# Pi3B__Adapter.net
KiCad netlist of a schematic drawn in EAGLE
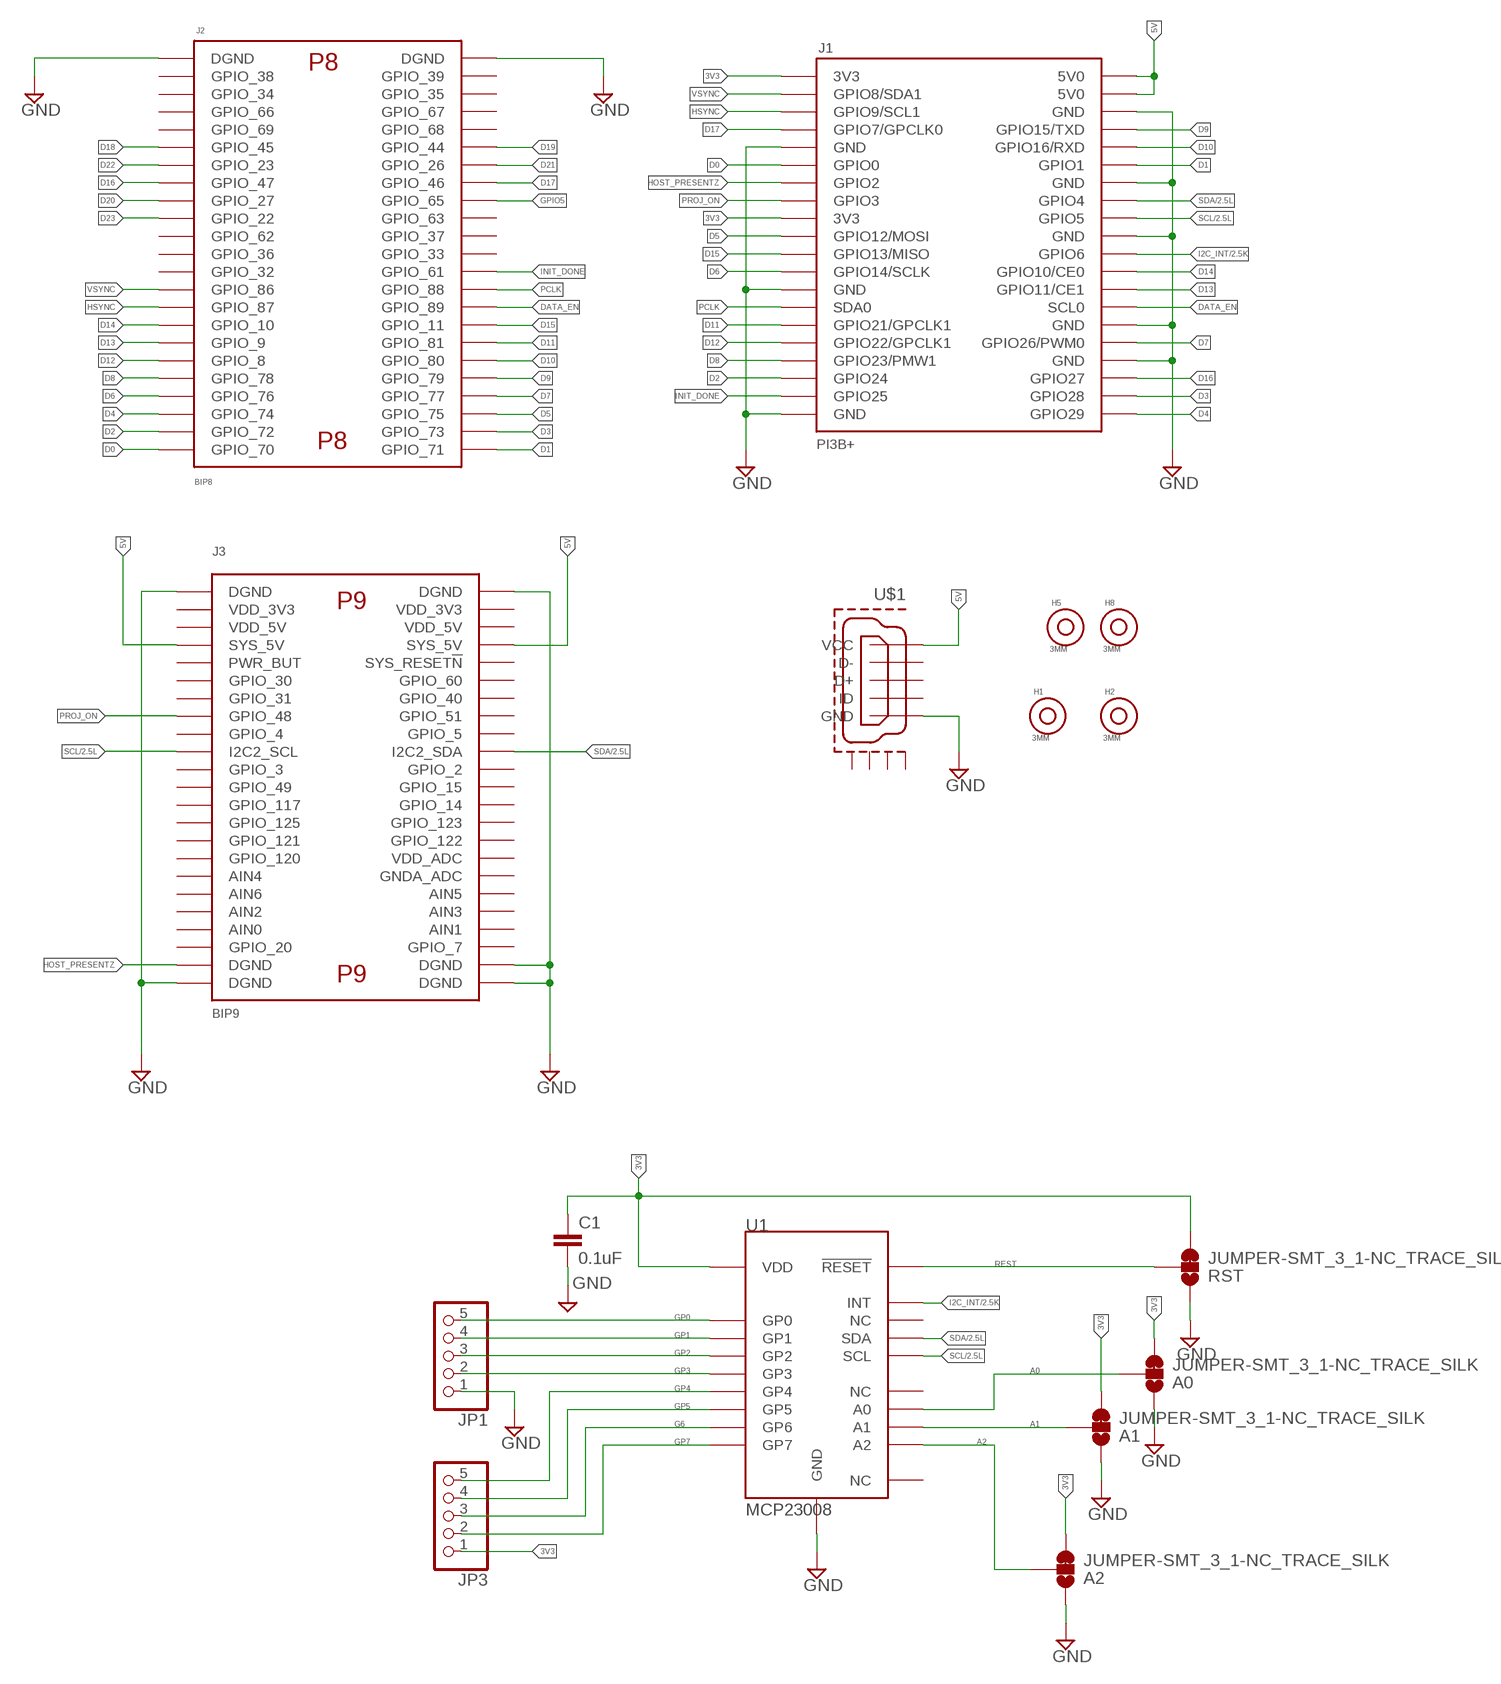
[diagram p0: schematic, sheet 1]

(export (version "E")
  (design (tool "Eeschema 10.0.6"))
  (components
    (comp (ref "A0")
      (value "JUMPER-SMT_3_1-NC_TRACE_SILK")
      (footprint "eagle-import:SMT-JUMPER_3_1-NC_TRACE_SILK")
      (libsource (lib "eagle-import") (part "JUMPER-SMT_3_1-NC_TRACE_SILK"))
    )
    (comp (ref "A1")
      (value "JUMPER-SMT_3_1-NC_TRACE_SILK")
      (footprint "eagle-import:SMT-JUMPER_3_1-NC_TRACE_SILK")
      (libsource (lib "eagle-import") (part "JUMPER-SMT_3_1-NC_TRACE_SILK"))
    )
    (comp (ref "A2")
      (value "JUMPER-SMT_3_1-NC_TRACE_SILK")
      (footprint "eagle-import:SMT-JUMPER_3_1-NC_TRACE_SILK")
      (libsource (lib "eagle-import") (part "JUMPER-SMT_3_1-NC_TRACE_SILK"))
    )
    (comp (ref "C1")
      (value "0.1uF")
      (footprint "eagle-import:0402")
      (libsource (lib "eagle-import") (part "0.1UF-0402-16V-10%"))
    )
    (comp (ref "H1")
      (value "3MM")
      (footprint "eagle-import:3MM")
      (libsource (lib "eagle-import") (part "3MM"))
    )
    (comp (ref "H2")
      (value "3MM")
      (footprint "eagle-import:3MM")
      (libsource (lib "eagle-import") (part "3MM"))
    )
    (comp (ref "H5")
      (value "3MM")
      (footprint "eagle-import:3MM")
      (libsource (lib "eagle-import") (part "3MM"))
    )
    (comp (ref "H8")
      (value "3MM")
      (footprint "eagle-import:3MM")
      (libsource (lib "eagle-import") (part "3MM"))
    )
    (comp (ref "J1")
      (value "PI3B+")
      (footprint "eagle-import:PI3B+")
      (libsource (lib "eagle-import") (part "PI3B+"))
    )
    (comp (ref "J2")
      (value "BIP8")
      (footprint "eagle-import:BIP8")
      (libsource (lib "eagle-import") (part "BIP8"))
    )
    (comp (ref "J3")
      (value "BIP9")
      (footprint "eagle-import:BIP9")
      (libsource (lib "eagle-import") (part "BIP9"))
    )
    (comp (ref "JP1")
      (value "PINHD-1X55X2MM")
      (footprint "eagle-import:1_05X2MM")
      (libsource (lib "eagle-import") (part "PINHD-1X55X2MM"))
    )
    (comp (ref "JP3")
      (value "PINHD-1X55X2MM")
      (footprint "eagle-import:1_05X2MM")
      (libsource (lib "eagle-import") (part "PINHD-1X55X2MM"))
    )
    (comp (ref "RST")
      (value "JUMPER-SMT_3_1-NC_TRACE_SILK")
      (footprint "eagle-import:SMT-JUMPER_3_1-NC_TRACE_SILK")
      (libsource (lib "eagle-import") (part "JUMPER-SMT_3_1-NC_TRACE_SILK"))
    )
    (comp (ref "U$1")
      (value "MICRO-USB-RECEPTACLE47589-0001")
      (footprint "eagle-import:47589-0001")
      (libsource (lib "eagle-import") (part "MICRO-USB-RECEPTACLE47589-0001"))
    )
    (comp (ref "U1")
      (value "MCP23008")
      (footprint "eagle-import:MCP23008SS")
      (libsource (lib "eagle-import") (part "MCP23008"))
    )
  )
  (nets
    (net (code "1") (name "/A0") (class "Default")
      (node (ref "A0") (pin "2") (pinfunction "2_2") (pintype "passive"))
      (node (ref "U1") (pin "A0") (pinfunction "A0_A0") (pintype "bidirectional"))
    )
    (net (code "2") (name "/A1") (class "Default")
      (node (ref "A1") (pin "2") (pinfunction "2_2") (pintype "passive"))
      (node (ref "U1") (pin "A1") (pinfunction "A1_A1") (pintype "bidirectional"))
    )
    (net (code "3") (name "/A2") (class "Default")
      (node (ref "A2") (pin "2") (pinfunction "2_2") (pintype "passive"))
      (node (ref "U1") (pin "A2") (pinfunction "A2_A2") (pintype "bidirectional"))
    )
    (net (code "4") (name "/G6") (class "Default")
      (node (ref "JP3") (pin "3") (pinfunction "3_3") (pintype "passive"))
      (node (ref "U1") (pin "GP6") (pinfunction "GP6_GP6") (pintype "bidirectional"))
    )
    (net (code "5") (name "/GP0") (class "Default")
      (node (ref "JP1") (pin "5") (pinfunction "5_5") (pintype "passive"))
      (node (ref "U1") (pin "GP0") (pinfunction "GP0_GP0") (pintype "bidirectional"))
    )
    (net (code "6") (name "/GP1") (class "Default")
      (node (ref "JP1") (pin "4") (pinfunction "4_4") (pintype "passive"))
      (node (ref "U1") (pin "GP1") (pinfunction "GP1_GP1") (pintype "bidirectional"))
    )
    (net (code "7") (name "/GP2") (class "Default")
      (node (ref "JP1") (pin "3") (pinfunction "3_3") (pintype "passive"))
      (node (ref "U1") (pin "GP2") (pinfunction "GP2_GP2") (pintype "bidirectional"))
    )
    (net (code "8") (name "/GP3") (class "Default")
      (node (ref "JP1") (pin "2") (pinfunction "2_2") (pintype "passive"))
      (node (ref "U1") (pin "GP3") (pinfunction "GP3_GP3") (pintype "bidirectional"))
    )
    (net (code "9") (name "/GP4") (class "Default")
      (node (ref "JP3") (pin "5") (pinfunction "5_5") (pintype "passive"))
      (node (ref "U1") (pin "GP4") (pinfunction "GP4_GP4") (pintype "bidirectional"))
    )
    (net (code "10") (name "/GP5") (class "Default")
      (node (ref "JP3") (pin "4") (pinfunction "4_4") (pintype "passive"))
      (node (ref "U1") (pin "GP5") (pinfunction "GP5_GP5") (pintype "bidirectional"))
    )
    (net (code "11") (name "/GP7") (class "Default")
      (node (ref "JP3") (pin "2") (pinfunction "2_2") (pintype "passive"))
      (node (ref "U1") (pin "GP7") (pinfunction "GP7_GP7") (pintype "bidirectional"))
    )
    (net (code "12") (name "/REST") (class "Default")
      (node (ref "RST") (pin "2") (pinfunction "2_2") (pintype "passive"))
      (node (ref "U1") (pin "!RESET") (pinfunction "~{RESET}_!RESET") (pintype "bidirectional"))
    )
    (net (code "13") (name "3V3") (class "Default")
      (node (ref "A0") (pin "3") (pinfunction "3_3") (pintype "passive"))
      (node (ref "A1") (pin "3") (pinfunction "3_3") (pintype "passive"))
      (node (ref "A2") (pin "3") (pinfunction "3_3") (pintype "passive"))
      (node (ref "C1") (pin "1") (pinfunction "1_1") (pintype "passive"))
      (node (ref "J1") (pin "3V3") (pinfunction "3V3_3V3") (pintype "bidirectional"))
      (node (ref "J1") (pin "3V3@1") (pinfunction "3V3_3V3@1") (pintype "bidirectional"))
      (node (ref "JP3") (pin "1") (pinfunction "1_1") (pintype "passive"))
      (node (ref "RST") (pin "3") (pinfunction "3_3") (pintype "passive"))
      (node (ref "U1") (pin "VDD") (pinfunction "VDD_VDD") (pintype "bidirectional"))
    )
    (net (code "14") (name "5V") (class "Default")
      (node (ref "J1") (pin "5V0") (pinfunction "5V0_5V0") (pintype "bidirectional"))
      (node (ref "J1") (pin "5V0@1") (pinfunction "5V0_5V0@1") (pintype "bidirectional"))
      (node (ref "J3") (pin "SYS_5V") (pinfunction "SYS_5V_SYS_5V") (pintype "bidirectional"))
      (node (ref "J3") (pin "SYS_5V@1") (pinfunction "SYS_5V_SYS_5V@1") (pintype "bidirectional"))
      (node (ref "U$1") (pin "V-BUS") (pinfunction "VCC_V-BUS") (pintype "input"))
    )
    (net (code "15") (name "D0") (class "Default")
      (node (ref "J1") (pin "GPIO0") (pinfunction "GPIO0_GPIO0") (pintype "bidirectional"))
      (node (ref "J2") (pin "GPIO_70") (pinfunction "GPIO_70_GPIO_70") (pintype "bidirectional"))
    )
    (net (code "16") (name "D1") (class "Default")
      (node (ref "J1") (pin "GPIO1") (pinfunction "GPIO1_GPIO1") (pintype "bidirectional"))
      (node (ref "J2") (pin "GPIO_71") (pinfunction "GPIO_71_GPIO_71") (pintype "bidirectional"))
    )
    (net (code "17") (name "D2") (class "Default")
      (node (ref "J1") (pin "GPIO24") (pinfunction "GPIO24_GPIO24") (pintype "bidirectional"))
      (node (ref "J2") (pin "GPIO_72") (pinfunction "GPIO_72_GPIO_72") (pintype "bidirectional"))
    )
    (net (code "18") (name "D3") (class "Default")
      (node (ref "J1") (pin "GPIO28") (pinfunction "GPIO28_GPIO28") (pintype "bidirectional"))
      (node (ref "J2") (pin "GPIO_73") (pinfunction "GPIO_73_GPIO_73") (pintype "bidirectional"))
    )
    (net (code "19") (name "D4") (class "Default")
      (node (ref "J1") (pin "GPIO29") (pinfunction "GPIO29_GPIO29") (pintype "bidirectional"))
      (node (ref "J2") (pin "GPIO_74") (pinfunction "GPIO_74_GPIO_74") (pintype "bidirectional"))
    )
    (net (code "20") (name "D5") (class "Default")
      (node (ref "J1") (pin "GPIO12/MOSI") (pinfunction "GPIO12/MOSI_GPIO12/MOSI") (pintype "bidirectional"))
      (node (ref "J2") (pin "GPIO_75") (pinfunction "GPIO_75_GPIO_75") (pintype "bidirectional"))
    )
    (net (code "21") (name "D6") (class "Default")
      (node (ref "J1") (pin "GPIO14/SCLK") (pinfunction "GPIO14/SCLK_GPIO14/SCLK") (pintype "bidirectional"))
      (node (ref "J2") (pin "GPIO_76") (pinfunction "GPIO_76_GPIO_76") (pintype "bidirectional"))
    )
    (net (code "22") (name "D7") (class "Default")
      (node (ref "J1") (pin "GPIO26/PMW0") (pinfunction "GPIO26/PWM0_GPIO26/PMW0") (pintype "bidirectional"))
      (node (ref "J2") (pin "GPIO_77") (pinfunction "GPIO_77_GPIO_77") (pintype "bidirectional"))
    )
    (net (code "23") (name "D8") (class "Default")
      (node (ref "J1") (pin "GPIO23/PWM1") (pinfunction "GPIO23/PMW1_GPIO23/PWM1") (pintype "bidirectional"))
      (node (ref "J2") (pin "GPIO_78") (pinfunction "GPIO_78_GPIO_78") (pintype "bidirectional"))
    )
    (net (code "24") (name "D9") (class "Default")
      (node (ref "J1") (pin "GPIO15/TXD") (pinfunction "GPIO15/TXD_GPIO15/TXD") (pintype "bidirectional"))
      (node (ref "J2") (pin "GPIO_79") (pinfunction "GPIO_79_GPIO_79") (pintype "bidirectional"))
    )
    (net (code "25") (name "D10") (class "Default")
      (node (ref "J1") (pin "GPIO16/RXD") (pinfunction "GPIO16/RXD_GPIO16/RXD") (pintype "bidirectional"))
      (node (ref "J2") (pin "GPIO_80") (pinfunction "GPIO_80_GPIO_80") (pintype "bidirectional"))
    )
    (net (code "26") (name "D11") (class "Default")
      (node (ref "J1") (pin "GPIO21/GPCLK1") (pinfunction "GPIO21/GPCLK1_GPIO21/GPCLK1") (pintype "bidirectional"))
      (node (ref "J2") (pin "GPIO_81") (pinfunction "GPIO_81_GPIO_81") (pintype "bidirectional"))
    )
    (net (code "27") (name "D12") (class "Default")
      (node (ref "J1") (pin "GPIO22/GPCLK2") (pinfunction "GPIO22/GPCLK1_GPIO22/GPCLK2") (pintype "bidirectional"))
      (node (ref "J2") (pin "GPIO_8") (pinfunction "GPIO_8_GPIO_8") (pintype "bidirectional"))
    )
    (net (code "28") (name "D13") (class "Default")
      (node (ref "J1") (pin "GPIO11/CE1") (pinfunction "GPIO11/CE1_GPIO11/CE1") (pintype "bidirectional"))
      (node (ref "J2") (pin "GPIO_9") (pinfunction "GPIO_9_GPIO_9") (pintype "bidirectional"))
    )
    (net (code "29") (name "D14") (class "Default")
      (node (ref "J1") (pin "GPIO10/CE0") (pinfunction "GPIO10/CE0_GPIO10/CE0") (pintype "bidirectional"))
      (node (ref "J2") (pin "GPIO_10") (pinfunction "GPIO_10_GPIO_10") (pintype "bidirectional"))
    )
    (net (code "30") (name "D15") (class "Default")
      (node (ref "J1") (pin "GPIO13/MISO") (pinfunction "GPIO13/MISO_GPIO13/MISO") (pintype "bidirectional"))
      (node (ref "J2") (pin "GPIO_11") (pinfunction "GPIO_11_GPIO_11") (pintype "bidirectional"))
    )
    (net (code "31") (name "D16") (class "Default")
      (node (ref "J1") (pin "GPIO27") (pinfunction "GPIO27_GPIO27") (pintype "bidirectional"))
      (node (ref "J2") (pin "GPIO_47") (pinfunction "GPIO_47_GPIO_47") (pintype "bidirectional"))
    )
    (net (code "32") (name "D17") (class "Default")
      (node (ref "J1") (pin "GPIO7/GPCLK0") (pinfunction "GPIO7/GPCLK0_GPIO7/GPCLK0") (pintype "bidirectional"))
      (node (ref "J2") (pin "GPIO_46") (pinfunction "GPIO_46_GPIO_46") (pintype "bidirectional"))
    )
    (net (code "33") (name "D18") (class "Default")
      (node (ref "J2") (pin "GPIO_45") (pinfunction "GPIO_45_GPIO_45") (pintype "bidirectional"))
    )
    (net (code "34") (name "D19") (class "Default")
      (node (ref "J2") (pin "GPIO_44") (pinfunction "GPIO_44_GPIO_44") (pintype "bidirectional"))
    )
    (net (code "35") (name "D20") (class "Default")
      (node (ref "J2") (pin "GPIO_27") (pinfunction "GPIO_27_GPIO_27") (pintype "bidirectional"))
    )
    (net (code "36") (name "D21") (class "Default")
      (node (ref "J2") (pin "GPIO_26") (pinfunction "GPIO_26_GPIO_26") (pintype "bidirectional"))
    )
    (net (code "37") (name "D22") (class "Default")
      (node (ref "J2") (pin "GPIO_23") (pinfunction "GPIO_23_GPIO_23") (pintype "bidirectional"))
    )
    (net (code "38") (name "D23") (class "Default")
      (node (ref "J2") (pin "GPIO_22") (pinfunction "GPIO_22_GPIO_22") (pintype "bidirectional"))
    )
    (net (code "39") (name "DATA_EN") (class "Default")
      (node (ref "J1") (pin "SCL0") (pinfunction "SCL0_SCL0") (pintype "bidirectional"))
      (node (ref "J2") (pin "GPIO_89") (pinfunction "GPIO_89_GPIO_89") (pintype "bidirectional"))
    )
    (net (code "40") (name "GND") (class "Default")
      (node (ref "A0") (pin "1") (pinfunction "1_1") (pintype "passive"))
      (node (ref "A1") (pin "1") (pinfunction "1_1") (pintype "passive"))
      (node (ref "A2") (pin "1") (pinfunction "1_1") (pintype "passive"))
      (node (ref "C1") (pin "2") (pinfunction "2_2") (pintype "passive"))
      (node (ref "J1") (pin "GND") (pinfunction "GND_GND") (pintype "bidirectional"))
      (node (ref "J1") (pin "GND@1") (pinfunction "GND_GND@1") (pintype "bidirectional"))
      (node (ref "J1") (pin "GND@2") (pinfunction "GND_GND@2") (pintype "bidirectional"))
      (node (ref "J1") (pin "GND@3") (pinfunction "GND_GND@3") (pintype "bidirectional"))
      (node (ref "J1") (pin "GND@4") (pinfunction "GND_GND@4") (pintype "bidirectional"))
      (node (ref "J1") (pin "GND@5") (pinfunction "GND_GND@5") (pintype "bidirectional"))
      (node (ref "J1") (pin "GND@6") (pinfunction "GND_GND@6") (pintype "bidirectional"))
      (node (ref "J1") (pin "GND@7") (pinfunction "GND_GND@7") (pintype "bidirectional"))
      (node (ref "J2") (pin "DGND") (pinfunction "DGND_DGND") (pintype "bidirectional"))
      (node (ref "J2") (pin "DGND@1") (pinfunction "DGND_DGND@1") (pintype "bidirectional"))
      (node (ref "J3") (pin "DGND") (pinfunction "DGND_DGND") (pintype "bidirectional"))
      (node (ref "J3") (pin "DGND@1") (pinfunction "DGND_DGND@1") (pintype "bidirectional"))
      (node (ref "J3") (pin "DGND@4") (pinfunction "DGND_DGND@4") (pintype "bidirectional"))
      (node (ref "J3") (pin "DGND@5") (pinfunction "DGND_DGND@5") (pintype "bidirectional"))
      (node (ref "J3") (pin "DGND@6") (pinfunction "DGND_DGND@6") (pintype "bidirectional"))
      (node (ref "JP1") (pin "1") (pinfunction "1_1") (pintype "passive"))
      (node (ref "RST") (pin "1") (pinfunction "1_1") (pintype "passive"))
      (node (ref "U$1") (pin "GND") (pinfunction "GND_GND") (pintype "input"))
      (node (ref "U1") (pin "GND") (pinfunction "GND_GND") (pintype "bidirectional"))
    )
    (net (code "41") (name "GPIO5") (class "Default")
      (node (ref "J2") (pin "GPIO_65") (pinfunction "GPIO_65_GPIO_65") (pintype "bidirectional"))
    )
    (net (code "42") (name "HOST_PRESENTZ") (class "Default")
      (node (ref "J1") (pin "GPIO2") (pinfunction "GPIO2_GPIO2") (pintype "bidirectional"))
      (node (ref "J3") (pin "DGND@3") (pinfunction "DGND_DGND@3") (pintype "bidirectional"))
    )
    (net (code "43") (name "HSYNC") (class "Default")
      (node (ref "J1") (pin "GPIO9/SCL1") (pinfunction "GPIO9/SCL1_GPIO9/SCL1") (pintype "bidirectional"))
      (node (ref "J2") (pin "GPIO_87") (pinfunction "GPIO_87_GPIO_87") (pintype "bidirectional"))
    )
    (net (code "44") (name "I2C_INT{slash}2.5K") (class "Default")
      (node (ref "J1") (pin "GPIO6") (pinfunction "GPIO6_GPIO6") (pintype "bidirectional"))
      (node (ref "U1") (pin "INT") (pinfunction "INT_INT") (pintype "bidirectional"))
    )
    (net (code "45") (name "INIT_DONE") (class "Default")
      (node (ref "J1") (pin "GPIO25") (pinfunction "GPIO25_GPIO25") (pintype "bidirectional"))
      (node (ref "J2") (pin "GPIO_61") (pinfunction "GPIO_61_GPIO_61") (pintype "bidirectional"))
    )
    (net (code "46") (name "PCLK") (class "Default")
      (node (ref "J1") (pin "SDA0") (pinfunction "SDA0_SDA0") (pintype "bidirectional"))
      (node (ref "J2") (pin "GPIO_88") (pinfunction "GPIO_88_GPIO_88") (pintype "bidirectional"))
    )
    (net (code "47") (name "PROJ_ON") (class "Default")
      (node (ref "J1") (pin "GPIO3") (pinfunction "GPIO3_GPIO3") (pintype "bidirectional"))
      (node (ref "J3") (pin "GPIO_48") (pinfunction "GPIO_48_GPIO_48") (pintype "bidirectional"))
    )
    (net (code "48") (name "SCL{slash}2.5L") (class "Default")
      (node (ref "J1") (pin "GPIO5") (pinfunction "GPIO5_GPIO5") (pintype "bidirectional"))
      (node (ref "J3") (pin "I2C2_SCL") (pinfunction "I2C2_SCL_I2C2_SCL") (pintype "bidirectional"))
      (node (ref "U1") (pin "SCL") (pinfunction "SCL_SCL") (pintype "bidirectional"))
    )
    (net (code "49") (name "SDA{slash}2.5L") (class "Default")
      (node (ref "J1") (pin "GPIO4") (pinfunction "GPIO4_GPIO4") (pintype "bidirectional"))
      (node (ref "J3") (pin "I2C2_SDA") (pinfunction "I2C2_SDA_I2C2_SDA") (pintype "bidirectional"))
      (node (ref "U1") (pin "SDA") (pinfunction "SDA_SDA") (pintype "bidirectional"))
    )
    (net (code "50") (name "VSYNC") (class "Default")
      (node (ref "J1") (pin "GPIO8/SDA1") (pinfunction "GPIO8/SDA1_GPIO8/SDA1") (pintype "bidirectional"))
      (node (ref "J2") (pin "GPIO_86") (pinfunction "GPIO_86_GPIO_86") (pintype "bidirectional"))
    )
    (net (code "51") (name "unconnected-(J2-PadGPIO_32)") (class "Default")
      (node (ref "J2") (pin "GPIO_32") (pinfunction "GPIO_32_GPIO_32") (pintype "bidirectional"))
    )
    (net (code "52") (name "unconnected-(J2-PadGPIO_33)") (class "Default")
      (node (ref "J2") (pin "GPIO_33") (pinfunction "GPIO_33_GPIO_33") (pintype "bidirectional"))
    )
    (net (code "53") (name "unconnected-(J2-PadGPIO_34)") (class "Default")
      (node (ref "J2") (pin "GPIO_34") (pinfunction "GPIO_34_GPIO_34") (pintype "bidirectional"))
    )
    (net (code "54") (name "unconnected-(J2-PadGPIO_35)") (class "Default")
      (node (ref "J2") (pin "GPIO_35") (pinfunction "GPIO_35_GPIO_35") (pintype "bidirectional"))
    )
    (net (code "55") (name "unconnected-(J2-PadGPIO_36)") (class "Default")
      (node (ref "J2") (pin "GPIO_36") (pinfunction "GPIO_36_GPIO_36") (pintype "bidirectional"))
    )
    (net (code "56") (name "unconnected-(J2-PadGPIO_37)") (class "Default")
      (node (ref "J2") (pin "GPIO_37") (pinfunction "GPIO_37_GPIO_37") (pintype "bidirectional"))
    )
    (net (code "57") (name "unconnected-(J2-PadGPIO_38)") (class "Default")
      (node (ref "J2") (pin "GPIO_38") (pinfunction "GPIO_38_GPIO_38") (pintype "bidirectional"))
    )
    (net (code "58") (name "unconnected-(J2-PadGPIO_39)") (class "Default")
      (node (ref "J2") (pin "GPIO_39") (pinfunction "GPIO_39_GPIO_39") (pintype "bidirectional"))
    )
    (net (code "59") (name "unconnected-(J2-PadGPIO_62)") (class "Default")
      (node (ref "J2") (pin "GPIO_62") (pinfunction "GPIO_62_GPIO_62") (pintype "bidirectional"))
    )
    (net (code "60") (name "unconnected-(J2-PadGPIO_63)") (class "Default")
      (node (ref "J2") (pin "GPIO_63") (pinfunction "GPIO_63_GPIO_63") (pintype "bidirectional"))
    )
    (net (code "61") (name "unconnected-(J2-PadGPIO_66)") (class "Default")
      (node (ref "J2") (pin "GPIO_66") (pinfunction "GPIO_66_GPIO_66") (pintype "bidirectional"))
    )
    (net (code "62") (name "unconnected-(J2-PadGPIO_67)") (class "Default")
      (node (ref "J2") (pin "GPIO_67") (pinfunction "GPIO_67_GPIO_67") (pintype "bidirectional"))
    )
    (net (code "63") (name "unconnected-(J2-PadGPIO_68)") (class "Default")
      (node (ref "J2") (pin "GPIO_68") (pinfunction "GPIO_68_GPIO_68") (pintype "bidirectional"))
    )
    (net (code "64") (name "unconnected-(J2-PadGPIO_69)") (class "Default")
      (node (ref "J2") (pin "GPIO_69") (pinfunction "GPIO_69_GPIO_69") (pintype "bidirectional"))
    )
    (net (code "65") (name "unconnected-(J3-PadAIN0)") (class "Default")
      (node (ref "J3") (pin "AIN0") (pinfunction "AIN0_AIN0") (pintype "bidirectional"))
    )
    (net (code "66") (name "unconnected-(J3-PadAIN1)") (class "Default")
      (node (ref "J3") (pin "AIN1") (pinfunction "AIN1_AIN1") (pintype "bidirectional"))
    )
    (net (code "67") (name "unconnected-(J3-PadAIN2)") (class "Default")
      (node (ref "J3") (pin "AIN2") (pinfunction "AIN2_AIN2") (pintype "bidirectional"))
    )
    (net (code "68") (name "unconnected-(J3-PadAIN3)") (class "Default")
      (node (ref "J3") (pin "AIN3") (pinfunction "AIN3_AIN3") (pintype "bidirectional"))
    )
    (net (code "69") (name "unconnected-(J3-PadAIN4)") (class "Default")
      (node (ref "J3") (pin "AIN4") (pinfunction "AIN4_AIN4") (pintype "bidirectional"))
    )
    (net (code "70") (name "unconnected-(J3-PadAIN5)") (class "Default")
      (node (ref "J3") (pin "AIN5") (pinfunction "AIN5_AIN5") (pintype "bidirectional"))
    )
    (net (code "71") (name "unconnected-(J3-PadAIN6)") (class "Default")
      (node (ref "J3") (pin "AIN6") (pinfunction "AIN6_AIN6") (pintype "bidirectional"))
    )
    (net (code "72") (name "unconnected-(J3-PadGNDA_ADC)") (class "Default")
      (node (ref "J3") (pin "GNDA_ADC") (pinfunction "GNDA_ADC_GNDA_ADC") (pintype "bidirectional"))
    )
    (net (code "73") (name "unconnected-(J3-PadGPIO_2)") (class "Default")
      (node (ref "J3") (pin "GPIO_2") (pinfunction "GPIO_2_GPIO_2") (pintype "bidirectional"))
    )
    (net (code "74") (name "unconnected-(J3-PadGPIO_3)") (class "Default")
      (node (ref "J3") (pin "GPIO_3") (pinfunction "GPIO_3_GPIO_3") (pintype "bidirectional"))
    )
    (net (code "75") (name "unconnected-(J3-PadGPIO_4)") (class "Default")
      (node (ref "J3") (pin "GPIO_4") (pinfunction "GPIO_4_GPIO_4") (pintype "bidirectional"))
    )
    (net (code "76") (name "unconnected-(J3-PadGPIO_5)") (class "Default")
      (node (ref "J3") (pin "GPIO_5") (pinfunction "GPIO_5_GPIO_5") (pintype "bidirectional"))
    )
    (net (code "77") (name "unconnected-(J3-PadGPIO_7)") (class "Default")
      (node (ref "J3") (pin "GPIO_7") (pinfunction "GPIO_7_GPIO_7") (pintype "bidirectional"))
    )
    (net (code "78") (name "unconnected-(J3-PadGPIO_14)") (class "Default")
      (node (ref "J3") (pin "GPIO_14") (pinfunction "GPIO_14_GPIO_14") (pintype "bidirectional"))
    )
    (net (code "79") (name "unconnected-(J3-PadGPIO_15)") (class "Default")
      (node (ref "J3") (pin "GPIO_15") (pinfunction "GPIO_15_GPIO_15") (pintype "bidirectional"))
    )
    (net (code "80") (name "unconnected-(J3-PadGPIO_20)") (class "Default")
      (node (ref "J3") (pin "GPIO_20") (pinfunction "GPIO_20_GPIO_20") (pintype "bidirectional"))
    )
    (net (code "81") (name "unconnected-(J3-PadGPIO_30)") (class "Default")
      (node (ref "J3") (pin "GPIO_30") (pinfunction "GPIO_30_GPIO_30") (pintype "bidirectional"))
    )
    (net (code "82") (name "unconnected-(J3-PadGPIO_31)") (class "Default")
      (node (ref "J3") (pin "GPIO_31") (pinfunction "GPIO_31_GPIO_31") (pintype "bidirectional"))
    )
    (net (code "83") (name "unconnected-(J3-PadGPIO_40)") (class "Default")
      (node (ref "J3") (pin "GPIO_40") (pinfunction "GPIO_40_GPIO_40") (pintype "bidirectional"))
    )
    (net (code "84") (name "unconnected-(J3-PadGPIO_49)") (class "Default")
      (node (ref "J3") (pin "GPIO_49") (pinfunction "GPIO_49_GPIO_49") (pintype "bidirectional"))
    )
    (net (code "85") (name "unconnected-(J3-PadGPIO_51)") (class "Default")
      (node (ref "J3") (pin "GPIO_51") (pinfunction "GPIO_51_GPIO_51") (pintype "bidirectional"))
    )
    (net (code "86") (name "unconnected-(J3-PadGPIO_60)") (class "Default")
      (node (ref "J3") (pin "GPIO_60") (pinfunction "GPIO_60_GPIO_60") (pintype "bidirectional"))
    )
    (net (code "87") (name "unconnected-(J3-PadGPIO_117)") (class "Default")
      (node (ref "J3") (pin "GPIO_117") (pinfunction "GPIO_117_GPIO_117") (pintype "bidirectional"))
    )
    (net (code "88") (name "unconnected-(J3-PadGPIO_120)") (class "Default")
      (node (ref "J3") (pin "GPIO_120") (pinfunction "GPIO_120_GPIO_120") (pintype "bidirectional"))
    )
    (net (code "89") (name "unconnected-(J3-PadGPIO_121)") (class "Default")
      (node (ref "J3") (pin "GPIO_121") (pinfunction "GPIO_121_GPIO_121") (pintype "bidirectional"))
    )
    (net (code "90") (name "unconnected-(J3-PadGPIO_122)") (class "Default")
      (node (ref "J3") (pin "GPIO_122") (pinfunction "GPIO_122_GPIO_122") (pintype "bidirectional"))
    )
    (net (code "91") (name "unconnected-(J3-PadGPIO_123)") (class "Default")
      (node (ref "J3") (pin "GPIO_123") (pinfunction "GPIO_123_GPIO_123") (pintype "bidirectional"))
    )
    (net (code "92") (name "unconnected-(J3-PadGPIO_125)") (class "Default")
      (node (ref "J3") (pin "GPIO_125") (pinfunction "GPIO_125_GPIO_125") (pintype "bidirectional"))
    )
    (net (code "93") (name "unconnected-(J3-PadPWR_BUT)") (class "Default")
      (node (ref "J3") (pin "PWR_BUT") (pinfunction "PWR_BUT_PWR_BUT") (pintype "bidirectional"))
    )
    (net (code "94") (name "unconnected-(J3-PadVDD_3V3)") (class "Default")
      (node (ref "J3") (pin "VDD_3V3") (pinfunction "VDD_3V3_VDD_3V3") (pintype "bidirectional"))
    )
    (net (code "95") (name "unconnected-(J3-PadVDD_5V)") (class "Default")
      (node (ref "J3") (pin "VDD_5V") (pinfunction "VDD_5V_VDD_5V") (pintype "bidirectional"))
    )
    (net (code "96") (name "unconnected-(J3-PadVDD_ADC)") (class "Default")
      (node (ref "J3") (pin "VDD_ADC") (pinfunction "VDD_ADC_VDD_ADC") (pintype "bidirectional"))
    )
    (net (code "97") (name "unconnected-(J3-SYS_RESET~{N}-PadSYS_RESET!N)") (class "Default")
      (node (ref "J3") (pin "SYS_RESET!N") (pinfunction "SYS_RESET~{N}_SYS_RESET!N") (pintype "bidirectional"))
    )
    (net (code "98") (name "unconnected-(J3-VDD_3V3-PadVDD_3V3@1)") (class "Default")
      (node (ref "J3") (pin "VDD_3V3@1") (pinfunction "VDD_3V3_VDD_3V3@1") (pintype "bidirectional"))
    )
    (net (code "99") (name "unconnected-(J3-VDD_5V-PadVDD_5V@1)") (class "Default")
      (node (ref "J3") (pin "VDD_5V@1") (pinfunction "VDD_5V_VDD_5V@1") (pintype "bidirectional"))
    )
    (net (code "100") (name "unconnected-(U$1-GND1-PadCASING1)") (class "Default")
      (node (ref "U$1") (pin "CASING1") (pinfunction "GND1_CASING1") (pintype "bidirectional"))
    )
    (net (code "101") (name "unconnected-(U$1-GND2-PadCASING2)") (class "Default")
      (node (ref "U$1") (pin "CASING2") (pinfunction "GND2_CASING2") (pintype "bidirectional"))
    )
    (net (code "102") (name "unconnected-(U$1-GND3-PadCASING3)") (class "Default")
      (node (ref "U$1") (pin "CASING3") (pinfunction "GND3_CASING3") (pintype "bidirectional"))
    )
    (net (code "103") (name "unconnected-(U$1-GND4-PadCASING4)") (class "Default")
      (node (ref "U$1") (pin "CASING4") (pinfunction "GND4_CASING4") (pintype "bidirectional"))
    )
    (net (code "104") (name "unconnected-(U$1-PadD+)") (class "Default")
      (node (ref "U$1") (pin "D+") (pinfunction "D+_D+") (pintype "input"))
    )
    (net (code "105") (name "unconnected-(U$1-PadD-)") (class "Default")
      (node (ref "U$1") (pin "D-") (pinfunction "D-_D-") (pintype "input"))
    )
    (net (code "106") (name "unconnected-(U$1-PadID)") (class "Default")
      (node (ref "U$1") (pin "ID") (pinfunction "ID_ID") (pintype "input"))
    )
    (net (code "107") (name "unconnected-(U1-NC-PadNC@1)") (class "Default")
      (node (ref "U1") (pin "NC@1") (pinfunction "NC_NC@1") (pintype "bidirectional"))
    )
    (net (code "108") (name "unconnected-(U1-NC-PadNC@2)") (class "Default")
      (node (ref "U1") (pin "NC@2") (pinfunction "NC_NC@2") (pintype "bidirectional"))
    )
    (net (code "109") (name "unconnected-(U1-PadNC)") (class "Default")
      (node (ref "U1") (pin "NC") (pinfunction "NC_NC") (pintype "bidirectional"))
    )
  )
)
